# sensor_array.net
KiCad netlist of a schematic drawn in EAGLE
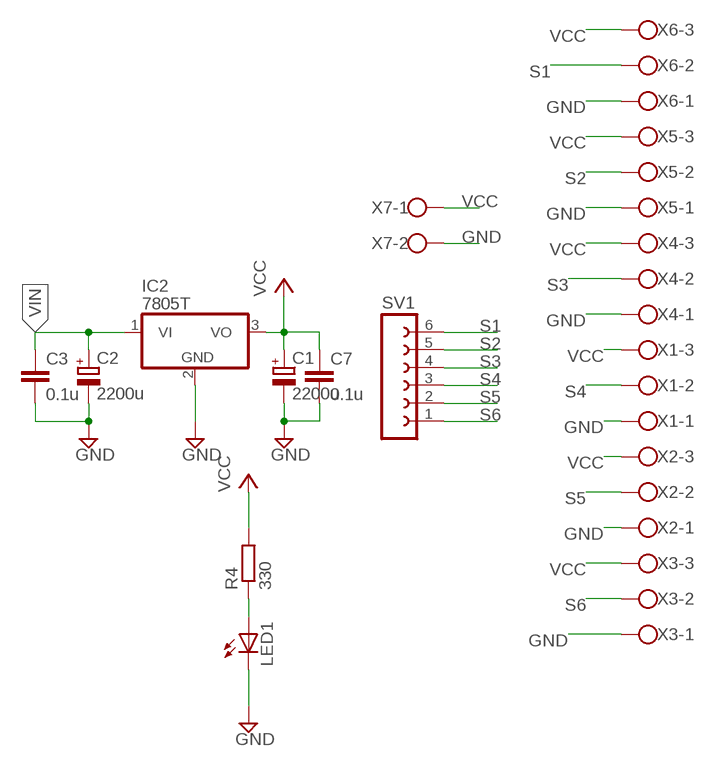
[diagram p0: schematic, sheet 1]

(export (version "E")
  (design (tool "Eeschema 10.0.6"))
  (components
    (comp (ref "C1")
      (value "2200u")
      (footprint "eagle-import:E5-10,5")
      (libsource (lib "eagle-import") (part "CPOL-EUE5-10.5"))
    )
    (comp (ref "C2")
      (value "2200u")
      (footprint "eagle-import:E5-10,5")
      (libsource (lib "eagle-import") (part "CPOL-EUE5-10.5"))
    )
    (comp (ref "C3")
      (value "0.1u")
      (footprint "eagle-import:C5B3")
      (libsource (lib "eagle-import") (part "C5/3"))
    )
    (comp (ref "C7")
      (value "0.1u")
      (footprint "eagle-import:C5B3")
      (libsource (lib "eagle-import") (part "C5/3"))
    )
    (comp (ref "IC2")
      (value "7805T")
      (footprint "eagle-import:TO220H")
      (libsource (lib "eagle-import") (part "78T05"))
    )
    (comp (ref "LED1")
      (value "LED5MM")
      (footprint "eagle-import:LED5MM")
      (libsource (lib "eagle-import") (part "LED5MM"))
    )
    (comp (ref "R4")
      (value "330")
      (footprint "eagle-import:0207_10")
      (libsource (lib "eagle-import") (part "R-EU_0207/10"))
    )
    (comp (ref "SV1")
      (value "FE06-1")
      (footprint "eagle-import:FE06")
      (libsource (lib "eagle-import") (part "FE06-1"))
    )
    (comp (ref "X1")
      (value "W237-103")
      (footprint "eagle-import:W237-103")
      (fields (field (name "MPN") "237-103"))
      (libsource (lib "eagle-import") (part "W237-103"))
    )
    (comp (ref "X2")
      (value "W237-103")
      (footprint "eagle-import:W237-103")
      (fields (field (name "MPN") "237-103"))
      (libsource (lib "eagle-import") (part "W237-103"))
    )
    (comp (ref "X3")
      (value "W237-103")
      (footprint "eagle-import:W237-103")
      (fields (field (name "MPN") "237-103"))
      (libsource (lib "eagle-import") (part "W237-103"))
    )
    (comp (ref "X4")
      (value "W237-103")
      (footprint "eagle-import:W237-103")
      (fields (field (name "MPN") "237-103"))
      (libsource (lib "eagle-import") (part "W237-103"))
    )
    (comp (ref "X5")
      (value "W237-103")
      (footprint "eagle-import:W237-103")
      (fields (field (name "MPN") "237-103"))
      (libsource (lib "eagle-import") (part "W237-103"))
    )
    (comp (ref "X6")
      (value "W237-103")
      (footprint "eagle-import:W237-103")
      (fields (field (name "MPN") "237-103"))
      (libsource (lib "eagle-import") (part "W237-103"))
    )
    (comp (ref "X7")
      (value "W237-102")
      (footprint "eagle-import:W237-102")
      (fields (field (name "MPN") "237-102"))
      (libsource (lib "eagle-import") (part "W237-102"))
    )
  )
  (nets
    (net (code "1") (name "/S1") (class "Default")
      (node (ref "SV1") (pin "6") (pinfunction "6_6") (pintype "passive"))
      (node (ref "X6") (pin "2") (pinfunction "KL_2") (pintype "passive"))
    )
    (net (code "2") (name "/S2") (class "Default")
      (node (ref "SV1") (pin "5") (pinfunction "5_5") (pintype "passive"))
      (node (ref "X5") (pin "2") (pinfunction "KL_2") (pintype "passive"))
    )
    (net (code "3") (name "/S3") (class "Default")
      (node (ref "SV1") (pin "4") (pinfunction "4_4") (pintype "passive"))
      (node (ref "X4") (pin "2") (pinfunction "KL_2") (pintype "passive"))
    )
    (net (code "4") (name "/S4") (class "Default")
      (node (ref "SV1") (pin "3") (pinfunction "3_3") (pintype "passive"))
      (node (ref "X1") (pin "2") (pinfunction "KL_2") (pintype "passive"))
    )
    (net (code "5") (name "/S5") (class "Default")
      (node (ref "SV1") (pin "2") (pinfunction "2_2") (pintype "passive"))
      (node (ref "X2") (pin "2") (pinfunction "KL_2") (pintype "passive"))
    )
    (net (code "6") (name "/S6") (class "Default")
      (node (ref "SV1") (pin "1") (pinfunction "1_1") (pintype "passive"))
      (node (ref "X3") (pin "2") (pinfunction "KL_2") (pintype "passive"))
    )
    (net (code "7") (name "GND") (class "Default")
      (node (ref "C1") (pin "-") (pinfunction "-_-") (pintype "passive"))
      (node (ref "C2") (pin "-") (pinfunction "-_-") (pintype "passive"))
      (node (ref "C3") (pin "2") (pinfunction "2_2") (pintype "passive"))
      (node (ref "C7") (pin "2") (pinfunction "2_2") (pintype "passive"))
      (node (ref "IC2") (pin "2") (pinfunction "GND_2") (pintype "passive"))
      (node (ref "LED1") (pin "K") (pinfunction "C_K") (pintype "passive"))
      (node (ref "X1") (pin "1") (pinfunction "KL_1") (pintype "passive"))
      (node (ref "X2") (pin "1") (pinfunction "KL_1") (pintype "passive"))
      (node (ref "X3") (pin "1") (pinfunction "KL_1") (pintype "passive"))
      (node (ref "X4") (pin "1") (pinfunction "KL_1") (pintype "passive"))
      (node (ref "X5") (pin "1") (pinfunction "KL_1") (pintype "passive"))
      (node (ref "X6") (pin "1") (pinfunction "KL_1") (pintype "passive"))
      (node (ref "X7") (pin "2") (pinfunction "KL_2") (pintype "passive"))
    )
    (net (code "8") (name "Net-(LED1-PadA)") (class "Default")
      (node (ref "LED1") (pin "A") (pinfunction "A_A") (pintype "passive"))
      (node (ref "R4") (pin "1") (pinfunction "1_1") (pintype "passive"))
    )
    (net (code "9") (name "VCC") (class "Default")
      (node (ref "C1") (pin "+") (pinfunction "+_+") (pintype "passive"))
      (node (ref "C7") (pin "1") (pinfunction "1_1") (pintype "passive"))
      (node (ref "IC2") (pin "3") (pinfunction "VO_3") (pintype "passive"))
      (node (ref "R4") (pin "2") (pinfunction "2_2") (pintype "passive"))
      (node (ref "X1") (pin "3") (pinfunction "KL_3") (pintype "passive"))
      (node (ref "X2") (pin "3") (pinfunction "KL_3") (pintype "passive"))
      (node (ref "X3") (pin "3") (pinfunction "KL_3") (pintype "passive"))
      (node (ref "X4") (pin "3") (pinfunction "KL_3") (pintype "passive"))
      (node (ref "X5") (pin "3") (pinfunction "KL_3") (pintype "passive"))
      (node (ref "X6") (pin "3") (pinfunction "KL_3") (pintype "passive"))
      (node (ref "X7") (pin "1") (pinfunction "KL_1") (pintype "passive"))
    )
    (net (code "10") (name "VIN") (class "Default")
      (node (ref "C2") (pin "+") (pinfunction "+_+") (pintype "passive"))
      (node (ref "C3") (pin "1") (pinfunction "1_1") (pintype "passive"))
      (node (ref "IC2") (pin "1") (pinfunction "VI_1") (pintype "input"))
    )
  )
)
